# ardiuno_shield.net
KiCad netlist of a schematic drawn in EAGLE
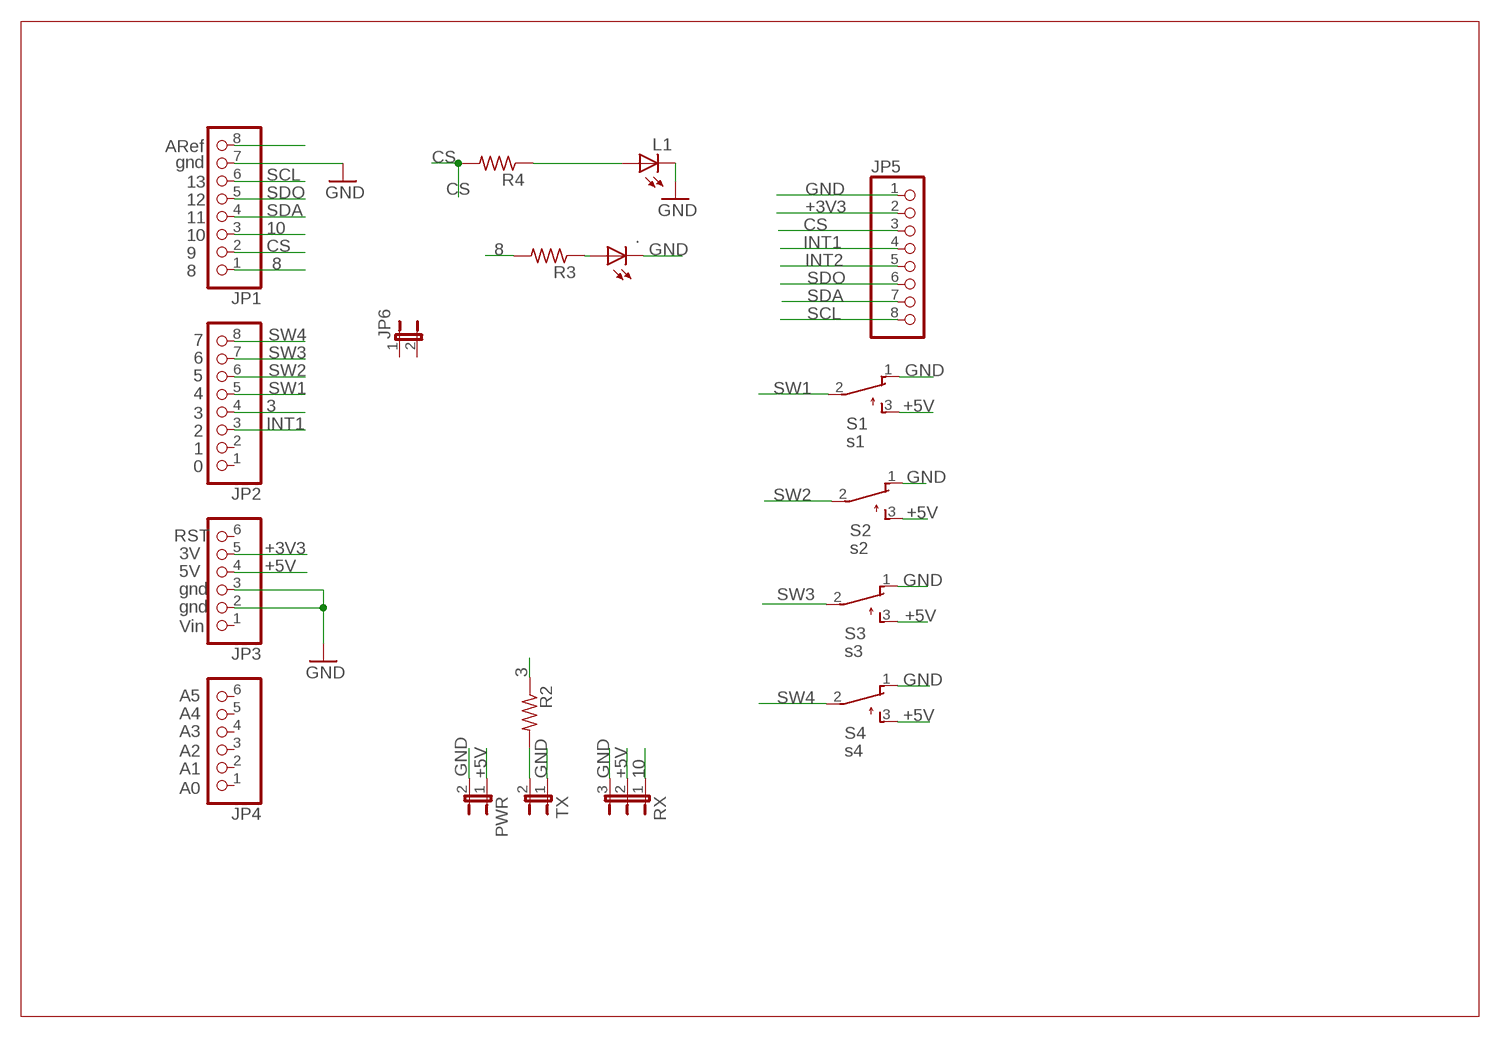
[diagram p0: schematic, sheet 1]

(export (version "E")
  (design (tool "Eeschema 10.0.6"))
  (components
    (comp (ref ".")
      (value "LED5MM")
      (footprint "eagle-import:LED5MM")
      (libsource (lib "eagle-import") (part "LED5MM"))
    )
    (comp (ref "JP1")
      (value "PINHD-1X8")
      (footprint "eagle-import:1X08")
      (libsource (lib "eagle-import") (part "PINHD-1X8"))
    )
    (comp (ref "JP2")
      (value "PINHD-1X8")
      (footprint "eagle-import:1X08")
      (libsource (lib "eagle-import") (part "PINHD-1X8"))
    )
    (comp (ref "JP3")
      (value "PINHD-1X6")
      (footprint "eagle-import:1X06")
      (libsource (lib "eagle-import") (part "PINHD-1X6"))
    )
    (comp (ref "JP4")
      (value "PINHD-1X6")
      (footprint "eagle-import:1X06")
      (libsource (lib "eagle-import") (part "PINHD-1X6"))
    )
    (comp (ref "JP5")
      (value "PINHD-1X8")
      (footprint "eagle-import:1X08")
      (libsource (lib "eagle-import") (part "PINHD-1X8"))
    )
    (comp (ref "JP6")
      (value "JP1E")
      (footprint "eagle-import:JP1")
      (libsource (lib "eagle-import") (part "JP1E"))
    )
    (comp (ref "L1")
      (value "LED5MM")
      (footprint "eagle-import:LED5MM")
      (libsource (lib "eagle-import") (part "LED5MM"))
    )
    (comp (ref "PWR")
      (value "JP1E")
      (footprint "eagle-import:JP1")
      (libsource (lib "eagle-import") (part "JP1E"))
    )
    (comp (ref "R2")
      (value "R-US_0207/10")
      (footprint "eagle-import:0207_10")
      (libsource (lib "eagle-import") (part "R-US_0207/10"))
    )
    (comp (ref "R3")
      (value "R-US_0207/10")
      (footprint "eagle-import:0207_10")
      (libsource (lib "eagle-import") (part "R-US_0207/10"))
    )
    (comp (ref "R4")
      (value "R-US_0207/10")
      (footprint "eagle-import:0207_10")
      (libsource (lib "eagle-import") (part "R-US_0207/10"))
    )
    (comp (ref "RX")
      (value "JP2E")
      (footprint "eagle-import:JP2")
      (libsource (lib "eagle-import") (part "JP2E"))
    )
    (comp (ref "S1")
      (value "s1")
      (footprint "eagle-import:TL3XPO")
      (libsource (lib "eagle-import") (part "TL32PO"))
    )
    (comp (ref "S2")
      (value "s2")
      (footprint "eagle-import:TL3XPO")
      (libsource (lib "eagle-import") (part "TL32PO"))
    )
    (comp (ref "S3")
      (value "s3")
      (footprint "eagle-import:TL3XPO")
      (libsource (lib "eagle-import") (part "TL32PO"))
    )
    (comp (ref "S4")
      (value "s4")
      (footprint "eagle-import:TL3XPO")
      (libsource (lib "eagle-import") (part "TL32PO"))
    )
    (comp (ref "TX")
      (value "JP1E")
      (footprint "eagle-import:JP1")
      (libsource (lib "eagle-import") (part "JP1E"))
    )
  )
  (nets
    (net (code "1") (name "/+3V3") (class "Default")
      (node (ref "JP3") (pin "5") (pinfunction "5_5") (pintype "passive"))
      (node (ref "JP5") (pin "2") (pinfunction "2_2") (pintype "passive"))
    )
    (net (code "2") (name "/+5V") (class "Default")
      (node (ref "JP3") (pin "4") (pinfunction "4_4") (pintype "passive"))
      (node (ref "PWR") (pin "1") (pinfunction "1_1") (pintype "passive"))
      (node (ref "RX") (pin "2") (pinfunction "2_2") (pintype "passive"))
      (node (ref "S1") (pin "3") (pinfunction "S_3") (pintype "passive"))
      (node (ref "S2") (pin "3") (pinfunction "S_3") (pintype "passive"))
      (node (ref "S3") (pin "3") (pinfunction "S_3") (pintype "passive"))
      (node (ref "S4") (pin "3") (pinfunction "S_3") (pintype "passive"))
    )
    (net (code "3") (name "/3") (class "Default")
      (node (ref "JP2") (pin "4") (pinfunction "4_4") (pintype "passive"))
      (node (ref "R2") (pin "1") (pinfunction "1_1") (pintype "passive"))
    )
    (net (code "4") (name "/8") (class "Default")
      (node (ref "JP1") (pin "1") (pinfunction "1_1") (pintype "passive"))
      (node (ref "R3") (pin "2") (pinfunction "2_2") (pintype "passive"))
    )
    (net (code "5") (name "/10") (class "Default")
      (node (ref "JP1") (pin "3") (pinfunction "3_3") (pintype "passive"))
      (node (ref "RX") (pin "1") (pinfunction "1_1") (pintype "passive"))
    )
    (net (code "6") (name "/CS") (class "Default")
      (node (ref "JP1") (pin "2") (pinfunction "2_2") (pintype "passive"))
      (node (ref "JP5") (pin "3") (pinfunction "3_3") (pintype "passive"))
      (node (ref "R4") (pin "2") (pinfunction "2_2") (pintype "passive"))
    )
    (net (code "7") (name "/INT1") (class "Default")
      (node (ref "JP2") (pin "3") (pinfunction "3_3") (pintype "passive"))
      (node (ref "JP5") (pin "4") (pinfunction "4_4") (pintype "passive"))
    )
    (net (code "8") (name "/INT2") (class "Default")
      (node (ref "JP5") (pin "5") (pinfunction "5_5") (pintype "passive"))
    )
    (net (code "9") (name "/SCL") (class "Default")
      (node (ref "JP1") (pin "6") (pinfunction "6_6") (pintype "passive"))
      (node (ref "JP5") (pin "8") (pinfunction "8_8") (pintype "passive"))
    )
    (net (code "10") (name "/SDA") (class "Default")
      (node (ref "JP1") (pin "4") (pinfunction "4_4") (pintype "passive"))
      (node (ref "JP5") (pin "7") (pinfunction "7_7") (pintype "passive"))
    )
    (net (code "11") (name "/SDO") (class "Default")
      (node (ref "JP1") (pin "5") (pinfunction "5_5") (pintype "passive"))
      (node (ref "JP5") (pin "6") (pinfunction "6_6") (pintype "passive"))
    )
    (net (code "12") (name "/SW1") (class "Default")
      (node (ref "JP2") (pin "5") (pinfunction "5_5") (pintype "passive"))
      (node (ref "S1") (pin "2") (pinfunction "P_2") (pintype "passive"))
    )
    (net (code "13") (name "/SW2") (class "Default")
      (node (ref "JP2") (pin "6") (pinfunction "6_6") (pintype "passive"))
      (node (ref "S2") (pin "2") (pinfunction "P_2") (pintype "passive"))
    )
    (net (code "14") (name "/SW3") (class "Default")
      (node (ref "JP2") (pin "7") (pinfunction "7_7") (pintype "passive"))
      (node (ref "S3") (pin "2") (pinfunction "P_2") (pintype "passive"))
    )
    (net (code "15") (name "/SW4") (class "Default")
      (node (ref "JP2") (pin "8") (pinfunction "8_8") (pintype "passive"))
      (node (ref "S4") (pin "2") (pinfunction "P_2") (pintype "passive"))
    )
    (net (code "16") (name "GND") (class "Default")
      (node (ref ".") (pin "K") (pinfunction "C_K") (pintype "passive"))
      (node (ref "JP1") (pin "7") (pinfunction "7_7") (pintype "passive"))
      (node (ref "JP3") (pin "2") (pinfunction "2_2") (pintype "passive"))
      (node (ref "JP3") (pin "3") (pinfunction "3_3") (pintype "passive"))
      (node (ref "JP5") (pin "1") (pinfunction "1_1") (pintype "passive"))
      (node (ref "L1") (pin "K") (pinfunction "C_K") (pintype "passive"))
      (node (ref "PWR") (pin "2") (pinfunction "2_2") (pintype "passive"))
      (node (ref "RX") (pin "3") (pinfunction "3_3") (pintype "passive"))
      (node (ref "S1") (pin "1") (pinfunction "O_1") (pintype "passive"))
      (node (ref "S2") (pin "1") (pinfunction "O_1") (pintype "passive"))
      (node (ref "S3") (pin "1") (pinfunction "O_1") (pintype "passive"))
      (node (ref "S4") (pin "1") (pinfunction "O_1") (pintype "passive"))
      (node (ref "TX") (pin "1") (pinfunction "1_1") (pintype "passive"))
    )
    (net (code "17") (name "Net-(.-PadA)") (class "Default")
      (node (ref ".") (pin "A") (pinfunction "A_A") (pintype "passive"))
      (node (ref "R3") (pin "1") (pinfunction "1_1") (pintype "passive"))
    )
    (net (code "18") (name "Net-(L1-PadA)") (class "Default")
      (node (ref "L1") (pin "A") (pinfunction "A_A") (pintype "passive"))
      (node (ref "R4") (pin "1") (pinfunction "1_1") (pintype "passive"))
    )
    (net (code "19") (name "Net-(R2-Pad2)") (class "Default")
      (node (ref "R2") (pin "2") (pinfunction "2_2") (pintype "passive"))
      (node (ref "TX") (pin "2") (pinfunction "2_2") (pintype "passive"))
    )
    (net (code "20") (name "unconnected-(JP1-Pad8)") (class "Default")
      (node (ref "JP1") (pin "8") (pinfunction "8_8") (pintype "passive"))
    )
    (net (code "21") (name "unconnected-(JP2-Pad1)") (class "Default")
      (node (ref "JP2") (pin "1") (pinfunction "1_1") (pintype "passive"))
    )
    (net (code "22") (name "unconnected-(JP2-Pad2)") (class "Default")
      (node (ref "JP2") (pin "2") (pinfunction "2_2") (pintype "passive"))
    )
    (net (code "23") (name "unconnected-(JP3-Pad1)") (class "Default")
      (node (ref "JP3") (pin "1") (pinfunction "1_1") (pintype "passive"))
    )
    (net (code "24") (name "unconnected-(JP3-Pad6)") (class "Default")
      (node (ref "JP3") (pin "6") (pinfunction "6_6") (pintype "passive"))
    )
    (net (code "25") (name "unconnected-(JP4-Pad1)") (class "Default")
      (node (ref "JP4") (pin "1") (pinfunction "1_1") (pintype "passive"))
    )
    (net (code "26") (name "unconnected-(JP4-Pad2)") (class "Default")
      (node (ref "JP4") (pin "2") (pinfunction "2_2") (pintype "passive"))
    )
    (net (code "27") (name "unconnected-(JP4-Pad3)") (class "Default")
      (node (ref "JP4") (pin "3") (pinfunction "3_3") (pintype "passive"))
    )
    (net (code "28") (name "unconnected-(JP4-Pad4)") (class "Default")
      (node (ref "JP4") (pin "4") (pinfunction "4_4") (pintype "passive"))
    )
    (net (code "29") (name "unconnected-(JP4-Pad5)") (class "Default")
      (node (ref "JP4") (pin "5") (pinfunction "5_5") (pintype "passive"))
    )
    (net (code "30") (name "unconnected-(JP4-Pad6)") (class "Default")
      (node (ref "JP4") (pin "6") (pinfunction "6_6") (pintype "passive"))
    )
    (net (code "31") (name "unconnected-(JP6-Pad1)") (class "Default")
      (node (ref "JP6") (pin "1") (pinfunction "1_1") (pintype "passive"))
    )
    (net (code "32") (name "unconnected-(JP6-Pad2)") (class "Default")
      (node (ref "JP6") (pin "2") (pinfunction "2_2") (pintype "passive"))
    )
  )
)
